# SAST_PCB_V2B_Test_Beta_Sensors_2.net
KiCad netlist of a schematic drawn in Altium Designer
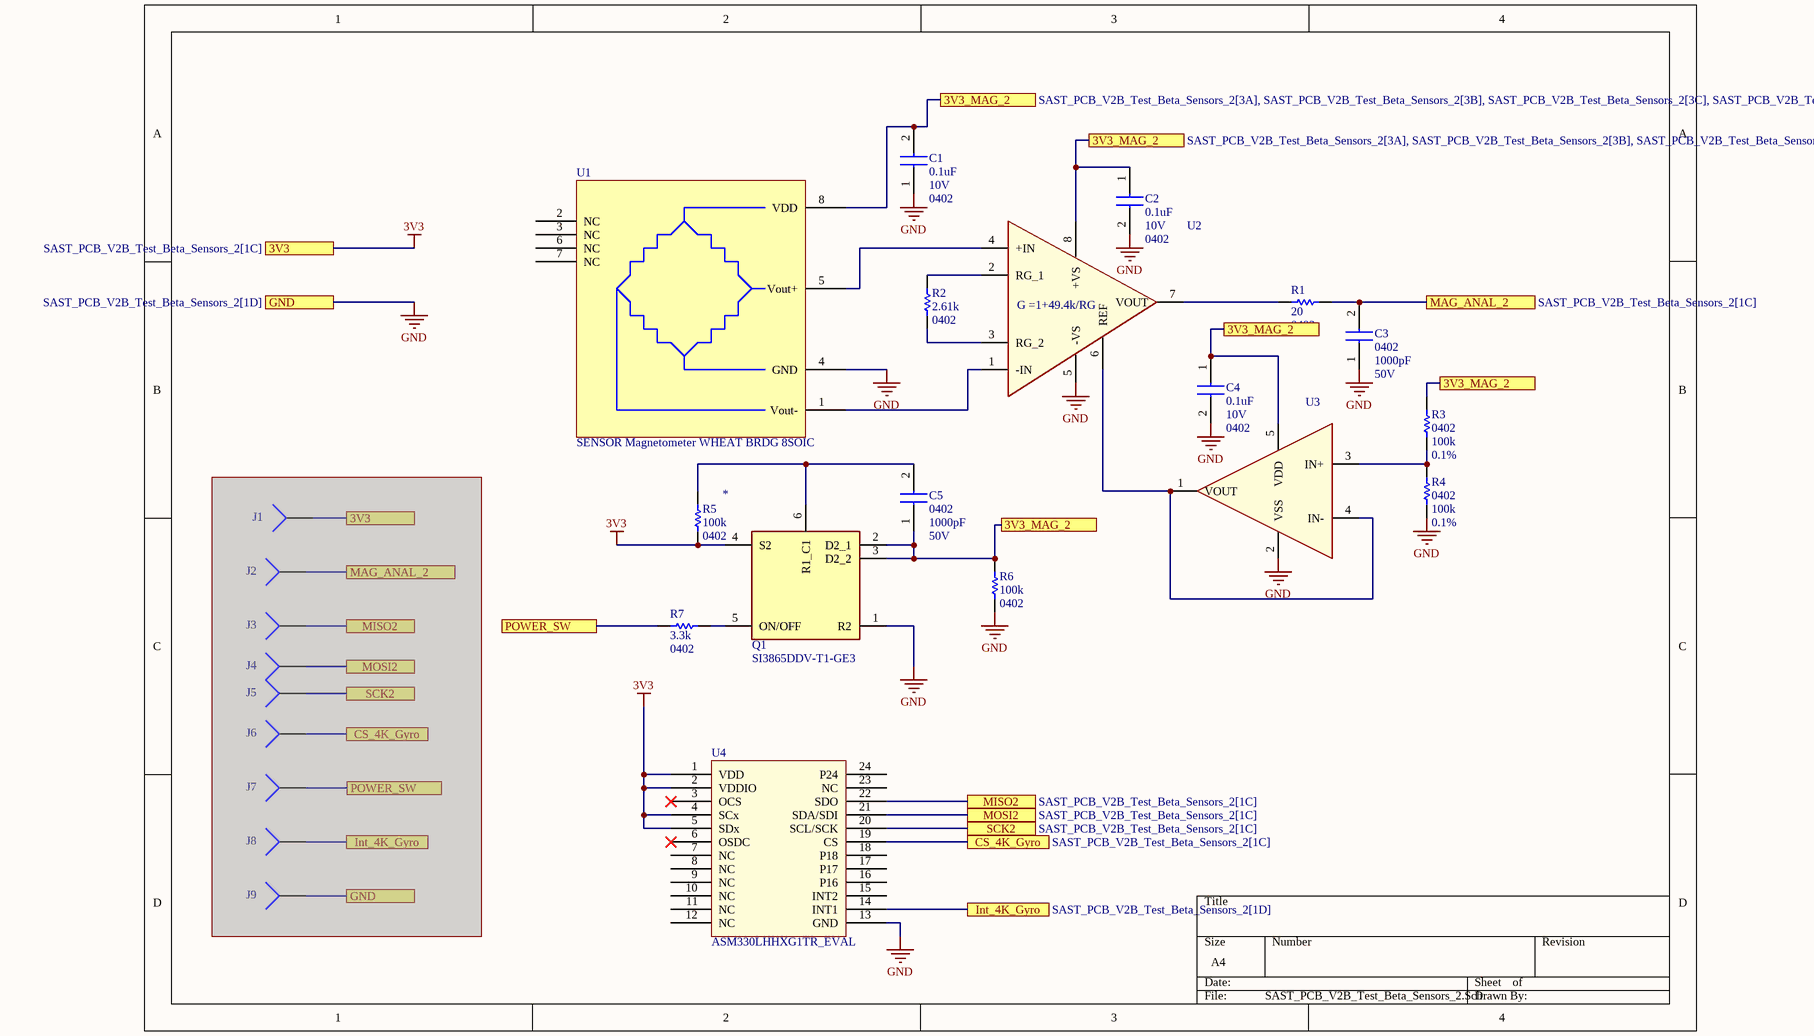
[diagram p0: SAST_PCB_V2B_Test_Beta_Sensors_2.SchDoc]

(export (version "E")
  (design (tool "Eeschema 10.0.6"))
  (components
    (comp (ref "C1")
      (value "0.1uF")
      (footprint "0402_DSP")
      (description "Capacitor: 0.1 µF ±10% 10V Ceramic Capacitor X8M 0201")
      (fields
        (field (name "MANUFACTURER_PART_NUMBER") "GCM033M8ED104KE07J")
        (field (name "MOUSER PART NUMBER") "81-GCM033M8ED104KE07")
        (field (name "VOLTAGE") "10V")
        (field (name "CASE/PACKAGE") "0402")
      )
      (libsource (lib "CS_Library") (part "GCM033M8ED104KE07J"))
    )
    (comp (ref "C2")
      (value "0.1uF")
      (footprint "0402_DSP")
      (description "Capacitor: 0.1 µF ±10% 10V Ceramic Capacitor X8M 0201")
      (fields
        (field (name "MANUFACTURER_PART_NUMBER") "GCM033M8ED104KE07J")
        (field (name "MOUSER PART NUMBER") "81-GCM033M8ED104KE07")
        (field (name "VOLTAGE") "10V")
        (field (name "CASE/PACKAGE") "0402")
      )
      (libsource (lib "CS_Library") (part "GCM033M8ED104KE07J"))
    )
    (comp (ref "C3")
      (value "1000pF")
      (footprint "0402_DSP")
      (description "Capacitor: 1000 pF ±10% 50V Ceramic Capacitor X8L 0402 (1005 Metric)")
      (fields
        (field (name "MANUFACTURER_PART_NUMBER") "GCM155L81H102KA37D")
        (field (name "MOUSER PART NUMBER") "81-GCM155L81H102KA7D")
        (field (name "CASE/PACKAGE") "0402")
        (field (name "VOLTAGE") "50V")
      )
      (libsource (lib "CS_Library") (part "GCM155L81H102KA37D"))
    )
    (comp (ref "C4")
      (value "0.1uF")
      (footprint "0402_DSP")
      (description "Capacitor: 0.1 µF ±10% 10V Ceramic Capacitor X8M 0201")
      (fields
        (field (name "MANUFACTURER_PART_NUMBER") "GCM033M8ED104KE07J")
        (field (name "MOUSER PART NUMBER") "81-GCM033M8ED104KE07")
        (field (name "VOLTAGE") "10V")
        (field (name "CASE/PACKAGE") "0402")
      )
      (libsource (lib "CS_Library") (part "GCM033M8ED104KE07J"))
    )
    (comp (ref "C5")
      (value "1000pF")
      (footprint "0402_DSP")
      (description "Capacitor: 1000 pF ±10% 50V Ceramic Capacitor X8L 0402 (1005 Metric)")
      (fields
        (field (name "MANUFACTURER_PART_NUMBER") "GCM155L81H102KA37D")
        (field (name "MOUSER PART NUMBER") "81-GCM155L81H102KA7D")
        (field (name "CASE/PACKAGE") "0402")
        (field (name "VOLTAGE") "50V")
      )
      (libsource (lib "CS_Library") (part "GCM155L81H102KA37D"))
    )
    (comp (ref "J1")
      (value "~")
      (footprint "Wire24Awg2x1HPAD")
      (description "Socket")
      (fields (field (name "PUBLISHER") "Altium Limited"))
      (libsource (lib "Miscellaneous Connectors") (part "Socket"))
    )
    (comp (ref "J2")
      (value "~")
      (footprint "Wire24Awg2x1HPAD")
      (description "Socket")
      (fields (field (name "PUBLISHER") "Altium Limited"))
      (libsource (lib "Miscellaneous Connectors") (part "Socket"))
    )
    (comp (ref "J3")
      (value "~")
      (footprint "Wire24Awg2x1HPAD")
      (description "Socket")
      (fields (field (name "PUBLISHER") "Altium Limited"))
      (libsource (lib "Miscellaneous Connectors") (part "Socket"))
    )
    (comp (ref "J4")
      (value "~")
      (footprint "Wire24Awg2x1HPAD")
      (description "Socket")
      (fields (field (name "PUBLISHER") "Altium Limited"))
      (libsource (lib "Miscellaneous Connectors") (part "Socket"))
    )
    (comp (ref "J5")
      (value "~")
      (footprint "Wire24Awg2x1HPAD")
      (description "Socket")
      (fields (field (name "PUBLISHER") "Altium Limited"))
      (libsource (lib "Miscellaneous Connectors") (part "Socket"))
    )
    (comp (ref "J6")
      (value "~")
      (footprint "Wire24Awg2x1HPAD")
      (description "Socket")
      (fields (field (name "PUBLISHER") "Altium Limited"))
      (libsource (lib "Miscellaneous Connectors") (part "Socket"))
    )
    (comp (ref "J7")
      (value "~")
      (footprint "Wire24Awg2x1HPAD")
      (description "Socket")
      (fields (field (name "PUBLISHER") "Altium Limited"))
      (libsource (lib "Miscellaneous Connectors") (part "Socket"))
    )
    (comp (ref "J8")
      (value "~")
      (footprint "Wire24Awg2x1HPAD")
      (description "Socket")
      (fields (field (name "PUBLISHER") "Altium Limited"))
      (libsource (lib "Miscellaneous Connectors") (part "Socket"))
    )
    (comp (ref "J9")
      (value "~")
      (footprint "Wire24Awg2x1HPAD")
      (description "Socket")
      (fields (field (name "PUBLISHER") "Altium Limited"))
      (libsource (lib "Miscellaneous Connectors") (part "Socket"))
    )
    (comp (ref "Q1")
      (value "SI3865DDV-T1-GE3")
      (footprint "CS_Library:SOP95P284X110-6N")
      (description "Transistor")
      (fields (field (name "MOUSER PART NUMBER") "78-SI3865DDV-T1-GE3") (field (name "CASE/PACKAGE") "*"))
      (libsource (lib "CS_Library") (part "SI3865DDV-T1-GE3"))
    )
    (comp (ref "R1")
      (value "20")
      (footprint "0402_DSP")
      (fields (field (name "CASE/PACKAGE") "0402"))
      (libsource (lib "CS_Library") (part "Resistor 0402"))
    )
    (comp (ref "R2")
      (value "2.61k")
      (footprint "0402_DSP")
      (fields (field (name "CASE/PACKAGE") "0402"))
      (libsource (lib "CS_Library") (part "Resistor 0402"))
    )
    (comp (ref "R3")
      (value "0402")
      (footprint "0402_DSP")
      (fields (field (name "ALTIUM_VALUE") "100k") (field (name "TOLERANCE") "0.1%"))
      (libsource (lib "CS_Library") (part "Resistor 0402"))
    )
    (comp (ref "R4")
      (value "0402")
      (footprint "0402_DSP")
      (fields (field (name "ALTIUM_VALUE") "100k") (field (name "TOLERANCE") "0.1%"))
      (libsource (lib "CS_Library") (part "Resistor 0402"))
    )
    (comp (ref "R5")
      (value "100k")
      (footprint "0402_DSP")
      (fields
        (field (name "MANUFACTURER_PART_NUMBER") "CRCW0402100KFKEDC")
        (field (name "CASE/PACKAGE") "0402")
      )
      (libsource (lib "CS_Library") (part "Resistor 0402"))
    )
    (comp (ref "R6")
      (value "100k")
      (footprint "0402_DSP")
      (fields
        (field (name "MANUFACTURER_PART_NUMBER") "CRCW0402100KFKEDC")
        (field (name "CASE/PACKAGE") "0402")
      )
      (libsource (lib "CS_Library") (part "Resistor 0402"))
    )
    (comp (ref "R7")
      (value "3.3k")
      (footprint "0402_DSP")
      (fields
        (field (name "MANUFACTURER_PART_NUMBER") "CRCW0402100KFKEDC")
        (field (name "CASE/PACKAGE") "0402")
      )
      (libsource (lib "CS_Library") (part "Resistor 0402"))
    )
    (comp (ref "U1")
      (value "SENSOR Magnetometer WHEAT BRDG 8SOIC")
      (footprint "SOIC127P600X175-8N")
      (description "Integrated Circuit: Magnetoresistive Sensor Single Axis 8-SOIC")
      (fields (field (name "MANUFACTURER_PART_NUMBER") "AAH002-02E"))
      (libsource (lib "CS_Library") (part "AAH002-02E"))
    )
    (comp (ref "U2")
      (value "IC INST AMP 1 CIRCUIT 8MSOP")
      (footprint "CS_Library:SOP65P490X110-8N")
      (description "Integrated Circuit: Instrumentation Amplifier 1 Circuit Rail-to-Rail 8-MSOP")
      (fields
        (field (name "MANUFACTURER_PART_NUMBER") "AD8226BRMZ-R7")
        (field (name "MOUSER PART NUMBER") "584-AD8226BRMZ-R7")
      )
      (libsource (lib "CS_Library") (part "AD8226BRMZ-R7"))
    )
    (comp (ref "U3")
      (value "IC OPAMP GP 1 CIRCUIT SOT23-5")
      (footprint "CS_Library:SOT95P270X145-5N")
      (description "Integrated Circuit: General Purpose Amplifier 1 Circuit Rail-to-Rail SOT-23-5")
      (fields
        (field (name "MANUFACTURER_PART_NUMBER") "MCP6401T-E/OT")
        (field (name "MOUSER PART NUMBER") "579-MCP6401T-E/OT")
      )
      (libsource (lib "CS_Library") (part "MCP6401T-E_OT"))
    )
    (comp (ref "U4")
      (value "ASM330LHHXG1TR_EVAL")
      (footprint "ASM330LHHX_Eval")
      (libsource (lib "CS_Library") (part "ASM330LHHXG1TR_EVAL"))
    )
  )
  (nets
    (net (code "1") (name "/3V3_MAG_2") (class "Default")
      (node (ref "C1") (pin "2") (pinfunction "2_2") (pintype "passive"))
      (node (ref "C2") (pin "1") (pinfunction "1_1") (pintype "passive"))
      (node (ref "C4") (pin "1") (pinfunction "1_1") (pintype "passive"))
      (node (ref "C5") (pin "1") (pinfunction "1_1") (pintype "passive"))
      (node (ref "Q1") (pin "2") (pinfunction "D2_1_2") (pintype "passive"))
      (node (ref "Q1") (pin "3") (pinfunction "D2_2_3") (pintype "passive"))
      (node (ref "R3") (pin "1") (pinfunction "1_1") (pintype "passive"))
      (node (ref "R6") (pin "2") (pinfunction "2_2") (pintype "passive"))
      (node (ref "U1") (pin "8") (pinfunction "VDD_8") (pintype "passive"))
      (node (ref "U2") (pin "8") (pinfunction "+VS_8") (pintype "passive"))
      (node (ref "U3") (pin "5") (pinfunction "VDD_5") (pintype "passive"))
    )
    (net (code "2") (name "/CS_4K_Gyro") (class "Default")
      (node (ref "J6") (pin "1") (pinfunction "1_1") (pintype "passive"))
      (node (ref "U4") (pin "19") (pinfunction "CS_19") (pintype "passive"))
    )
    (net (code "3") (name "/Int_4K_Gyro") (class "Default")
      (node (ref "J8") (pin "1") (pinfunction "1_1") (pintype "passive"))
      (node (ref "U4") (pin "14") (pinfunction "INT1_14") (pintype "passive"))
    )
    (net (code "4") (name "/MAG_ANAL_2") (class "Default")
      (node (ref "C3") (pin "2") (pinfunction "2_2") (pintype "passive"))
      (node (ref "J2") (pin "1") (pinfunction "1_1") (pintype "passive"))
      (node (ref "R1") (pin "1") (pinfunction "1_1") (pintype "passive"))
    )
    (net (code "5") (name "/MISO2") (class "Default")
      (node (ref "J3") (pin "1") (pinfunction "1_1") (pintype "passive"))
      (node (ref "U4") (pin "22") (pinfunction "SDO_22") (pintype "passive"))
    )
    (net (code "6") (name "/MOSI2") (class "Default")
      (node (ref "J4") (pin "1") (pinfunction "1_1") (pintype "passive"))
      (node (ref "U4") (pin "21") (pinfunction "SDA/SDI_21") (pintype "passive"))
    )
    (net (code "7") (name "/POWER_SW") (class "Default")
      (node (ref "J7") (pin "1") (pinfunction "1_1") (pintype "passive"))
      (node (ref "R7") (pin "2") (pinfunction "2_2") (pintype "passive"))
    )
    (net (code "8") (name "/SCK2") (class "Default")
      (node (ref "J5") (pin "1") (pinfunction "1_1") (pintype "passive"))
      (node (ref "U4") (pin "20") (pinfunction "SCL/SCK_20") (pintype "passive"))
    )
    (net (code "9") (name "3V3") (class "Default")
      (node (ref "J1") (pin "1") (pinfunction "1_1") (pintype "passive"))
      (node (ref "Q1") (pin "4") (pinfunction "S2_4") (pintype "passive"))
      (node (ref "R5") (pin "1") (pinfunction "1_1") (pintype "passive"))
      (node (ref "U4") (pin "1") (pinfunction "VDD_1") (pintype "passive"))
      (node (ref "U4") (pin "2") (pinfunction "VDDIO_2") (pintype "passive"))
      (node (ref "U4") (pin "4") (pinfunction "SCx_4") (pintype "passive"))
      (node (ref "U4") (pin "5") (pinfunction "SDx_5") (pintype "passive"))
    )
    (net (code "10") (name "GND") (class "Default")
      (node (ref "C1") (pin "1") (pinfunction "1_1") (pintype "passive"))
      (node (ref "C2") (pin "2") (pinfunction "2_2") (pintype "passive"))
      (node (ref "C3") (pin "1") (pinfunction "1_1") (pintype "passive"))
      (node (ref "C4") (pin "2") (pinfunction "2_2") (pintype "passive"))
      (node (ref "J9") (pin "1") (pinfunction "1_1") (pintype "passive"))
      (node (ref "Q1") (pin "1") (pinfunction "R2_1") (pintype "passive"))
      (node (ref "R4") (pin "2") (pinfunction "2_2") (pintype "passive"))
      (node (ref "R6") (pin "1") (pinfunction "1_1") (pintype "passive"))
      (node (ref "U1") (pin "4") (pinfunction "GND_4") (pintype "passive"))
      (node (ref "U2") (pin "5") (pinfunction "-VS_5") (pintype "passive"))
      (node (ref "U3") (pin "2") (pinfunction "VSS_2") (pintype "passive"))
      (node (ref "U4") (pin "13") (pinfunction "GND_13") (pintype "passive"))
    )
    (net (code "11") (name "Net-(Q1-ON{slash}OFF)") (class "Default")
      (node (ref "Q1") (pin "5") (pinfunction "ON/OFF_5") (pintype "passive"))
      (node (ref "R7") (pin "1") (pinfunction "1_1") (pintype "passive"))
    )
    (net (code "12") (name "Net-(Q1-R1_C1)") (class "Default")
      (node (ref "C5") (pin "2") (pinfunction "2_2") (pintype "passive"))
      (node (ref "Q1") (pin "6") (pinfunction "R1_C1_6") (pintype "passive"))
      (node (ref "R5") (pin "2") (pinfunction "2_2") (pintype "passive"))
    )
    (net (code "13") (name "Net-(U1-Vout+)") (class "Default")
      (node (ref "U1") (pin "5") (pinfunction "Vout+_5") (pintype "passive"))
      (node (ref "U2") (pin "4") (pinfunction "+IN_4") (pintype "passive"))
    )
    (net (code "14") (name "Net-(U1-Vout-)") (class "Default")
      (node (ref "U1") (pin "1") (pinfunction "Vout-_1") (pintype "passive"))
      (node (ref "U2") (pin "1") (pinfunction "-IN_1") (pintype "passive"))
    )
    (net (code "15") (name "Net-(U2-REF)") (class "Default")
      (node (ref "U2") (pin "6") (pinfunction "REF_6") (pintype "passive"))
      (node (ref "U3") (pin "1") (pinfunction "VOUT_1") (pintype "passive"))
      (node (ref "U3") (pin "4") (pinfunction "IN-_4") (pintype "passive"))
    )
    (net (code "16") (name "Net-(U2-RG_1)") (class "Default")
      (node (ref "R2") (pin "2") (pinfunction "2_2") (pintype "passive"))
      (node (ref "U2") (pin "2") (pinfunction "RG_1_2") (pintype "passive"))
    )
    (net (code "17") (name "Net-(U2-RG_2)") (class "Default")
      (node (ref "R2") (pin "1") (pinfunction "1_1") (pintype "passive"))
      (node (ref "U2") (pin "3") (pinfunction "RG_2_3") (pintype "passive"))
    )
    (net (code "18") (name "Net-(U2-VOUT)") (class "Default")
      (node (ref "R1") (pin "2") (pinfunction "2_2") (pintype "passive"))
      (node (ref "U2") (pin "7") (pinfunction "VOUT_7") (pintype "passive"))
    )
    (net (code "19") (name "Net-(U3-IN+)") (class "Default")
      (node (ref "R3") (pin "2") (pinfunction "2_2") (pintype "passive"))
      (node (ref "R4") (pin "1") (pinfunction "1_1") (pintype "passive"))
      (node (ref "U3") (pin "3") (pinfunction "IN+_3") (pintype "passive"))
    )
    (net (code "20") (name "unconnected-(U1-NC-Pad2)") (class "Default")
      (node (ref "U1") (pin "2") (pinfunction "NC_2") (pintype "passive"))
    )
    (net (code "21") (name "unconnected-(U1-NC-Pad3)") (class "Default")
      (node (ref "U1") (pin "3") (pinfunction "NC_3") (pintype "passive"))
    )
    (net (code "22") (name "unconnected-(U1-NC-Pad6)") (class "Default")
      (node (ref "U1") (pin "6") (pinfunction "NC_6") (pintype "passive"))
    )
    (net (code "23") (name "unconnected-(U1-NC-Pad7)") (class "Default")
      (node (ref "U1") (pin "7") (pinfunction "NC_7") (pintype "passive"))
    )
    (net (code "24") (name "unconnected-(U4-INT2-Pad15)") (class "Default")
      (node (ref "U4") (pin "15") (pinfunction "INT2_15") (pintype "passive"))
    )
    (net (code "25") (name "unconnected-(U4-NC-Pad7)") (class "Default")
      (node (ref "U4") (pin "7") (pinfunction "NC_7") (pintype "passive"))
    )
    (net (code "26") (name "unconnected-(U4-NC-Pad8)") (class "Default")
      (node (ref "U4") (pin "8") (pinfunction "NC_8") (pintype "passive"))
    )
    (net (code "27") (name "unconnected-(U4-NC-Pad9)") (class "Default")
      (node (ref "U4") (pin "9") (pinfunction "NC_9") (pintype "passive"))
    )
    (net (code "28") (name "unconnected-(U4-NC-Pad10)") (class "Default")
      (node (ref "U4") (pin "10") (pinfunction "NC_10") (pintype "passive"))
    )
    (net (code "29") (name "unconnected-(U4-NC-Pad11)") (class "Default")
      (node (ref "U4") (pin "11") (pinfunction "NC_11") (pintype "passive"))
    )
    (net (code "30") (name "unconnected-(U4-NC-Pad12)") (class "Default")
      (node (ref "U4") (pin "12") (pinfunction "NC_12") (pintype "passive"))
    )
    (net (code "31") (name "unconnected-(U4-NC-Pad23)") (class "Default")
      (node (ref "U4") (pin "23") (pinfunction "NC_23") (pintype "passive"))
    )
    (net (code "32") (name "unconnected-(U4-OCS-Pad3)") (class "Default")
      (node (ref "U4") (pin "3") (pinfunction "OCS_3") (pintype "passive+no_connect"))
    )
    (net (code "33") (name "unconnected-(U4-OSDC-Pad6)") (class "Default")
      (node (ref "U4") (pin "6") (pinfunction "OSDC_6") (pintype "passive+no_connect"))
    )
    (net (code "34") (name "unconnected-(U4-P16-Pad16)") (class "Default")
      (node (ref "U4") (pin "16") (pinfunction "P16_16") (pintype "passive"))
    )
    (net (code "35") (name "unconnected-(U4-P17-Pad17)") (class "Default")
      (node (ref "U4") (pin "17") (pinfunction "P17_17") (pintype "passive"))
    )
    (net (code "36") (name "unconnected-(U4-P18-Pad18)") (class "Default")
      (node (ref "U4") (pin "18") (pinfunction "P18_18") (pintype "passive"))
    )
    (net (code "37") (name "unconnected-(U4-P24-Pad24)") (class "Default")
      (node (ref "U4") (pin "24") (pinfunction "P24_24") (pintype "passive"))
    )
  )
)
